# Ultrasonico.net
KiCad netlist of a schematic drawn in EAGLE
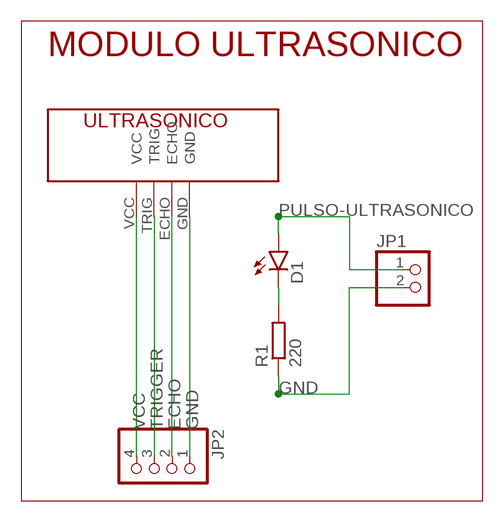
[diagram p0: schematic, sheet 1]

(export (version "E")
  (design (tool "Eeschema 10.0.6"))
  (components
    (comp (ref "D1")
      (value "LED3MM")
      (footprint "eagle-import:LED3MM")
      (libsource (lib "eagle-import") (part "LED3MM"))
    )
    (comp (ref "JP1")
      (value "PINHD-1X2")
      (footprint "eagle-import:1X02")
      (libsource (lib "eagle-import") (part "PINHD-1X2"))
    )
    (comp (ref "JP2")
      (value "PINHD-1X4")
      (footprint "eagle-import:1X04")
      (libsource (lib "eagle-import") (part "PINHD-1X4"))
    )
    (comp (ref "R1")
      (value "220")
      (footprint "eagle-import:0204_7")
      (libsource (lib "eagle-import") (part "R-EU_0204/7"))
    )
    (comp (ref "U$1")
      (value "ULTRASONICO")
      (footprint "eagle-import:ULTRASONICO")
      (libsource (lib "eagle-import") (part "ULTRASONICO"))
    )
  )
  (nets
    (net (code "1") (name "/ECHO") (class "Default")
      (node (ref "JP2") (pin "2") (pinfunction "2_2") (pintype "passive"))
      (node (ref "U$1") (pin "ECHO") (pinfunction "ECHO_ECHO") (pintype "bidirectional"))
    )
    (net (code "2") (name "/GND") (class "Default")
      (node (ref "JP1") (pin "2") (pinfunction "2_2") (pintype "passive"))
      (node (ref "JP2") (pin "1") (pinfunction "1_1") (pintype "passive"))
      (node (ref "R1") (pin "1") (pinfunction "1_1") (pintype "passive"))
      (node (ref "U$1") (pin "GND") (pinfunction "GND_GND") (pintype "bidirectional"))
    )
    (net (code "3") (name "/PULSO-ULTRASONICO") (class "Default")
      (node (ref "D1") (pin "A") (pinfunction "A_A") (pintype "passive"))
      (node (ref "JP1") (pin "1") (pinfunction "1_1") (pintype "passive"))
    )
    (net (code "4") (name "/TRIGGER") (class "Default")
      (node (ref "JP2") (pin "3") (pinfunction "3_3") (pintype "passive"))
      (node (ref "U$1") (pin "TRIG") (pinfunction "TRIG_TRIG") (pintype "bidirectional"))
    )
    (net (code "5") (name "/VCC") (class "Default")
      (node (ref "JP2") (pin "4") (pinfunction "4_4") (pintype "passive"))
      (node (ref "U$1") (pin "VCC") (pinfunction "VCC_VCC") (pintype "bidirectional"))
    )
    (net (code "6") (name "Net-(D1-C)") (class "Default")
      (node (ref "D1") (pin "K") (pinfunction "C_K") (pintype "passive"))
      (node (ref "R1") (pin "2") (pinfunction "2_2") (pintype "passive"))
    )
  )
)
